# CoffeeMakersch.net
KiCad netlist of a schematic drawn in EAGLE
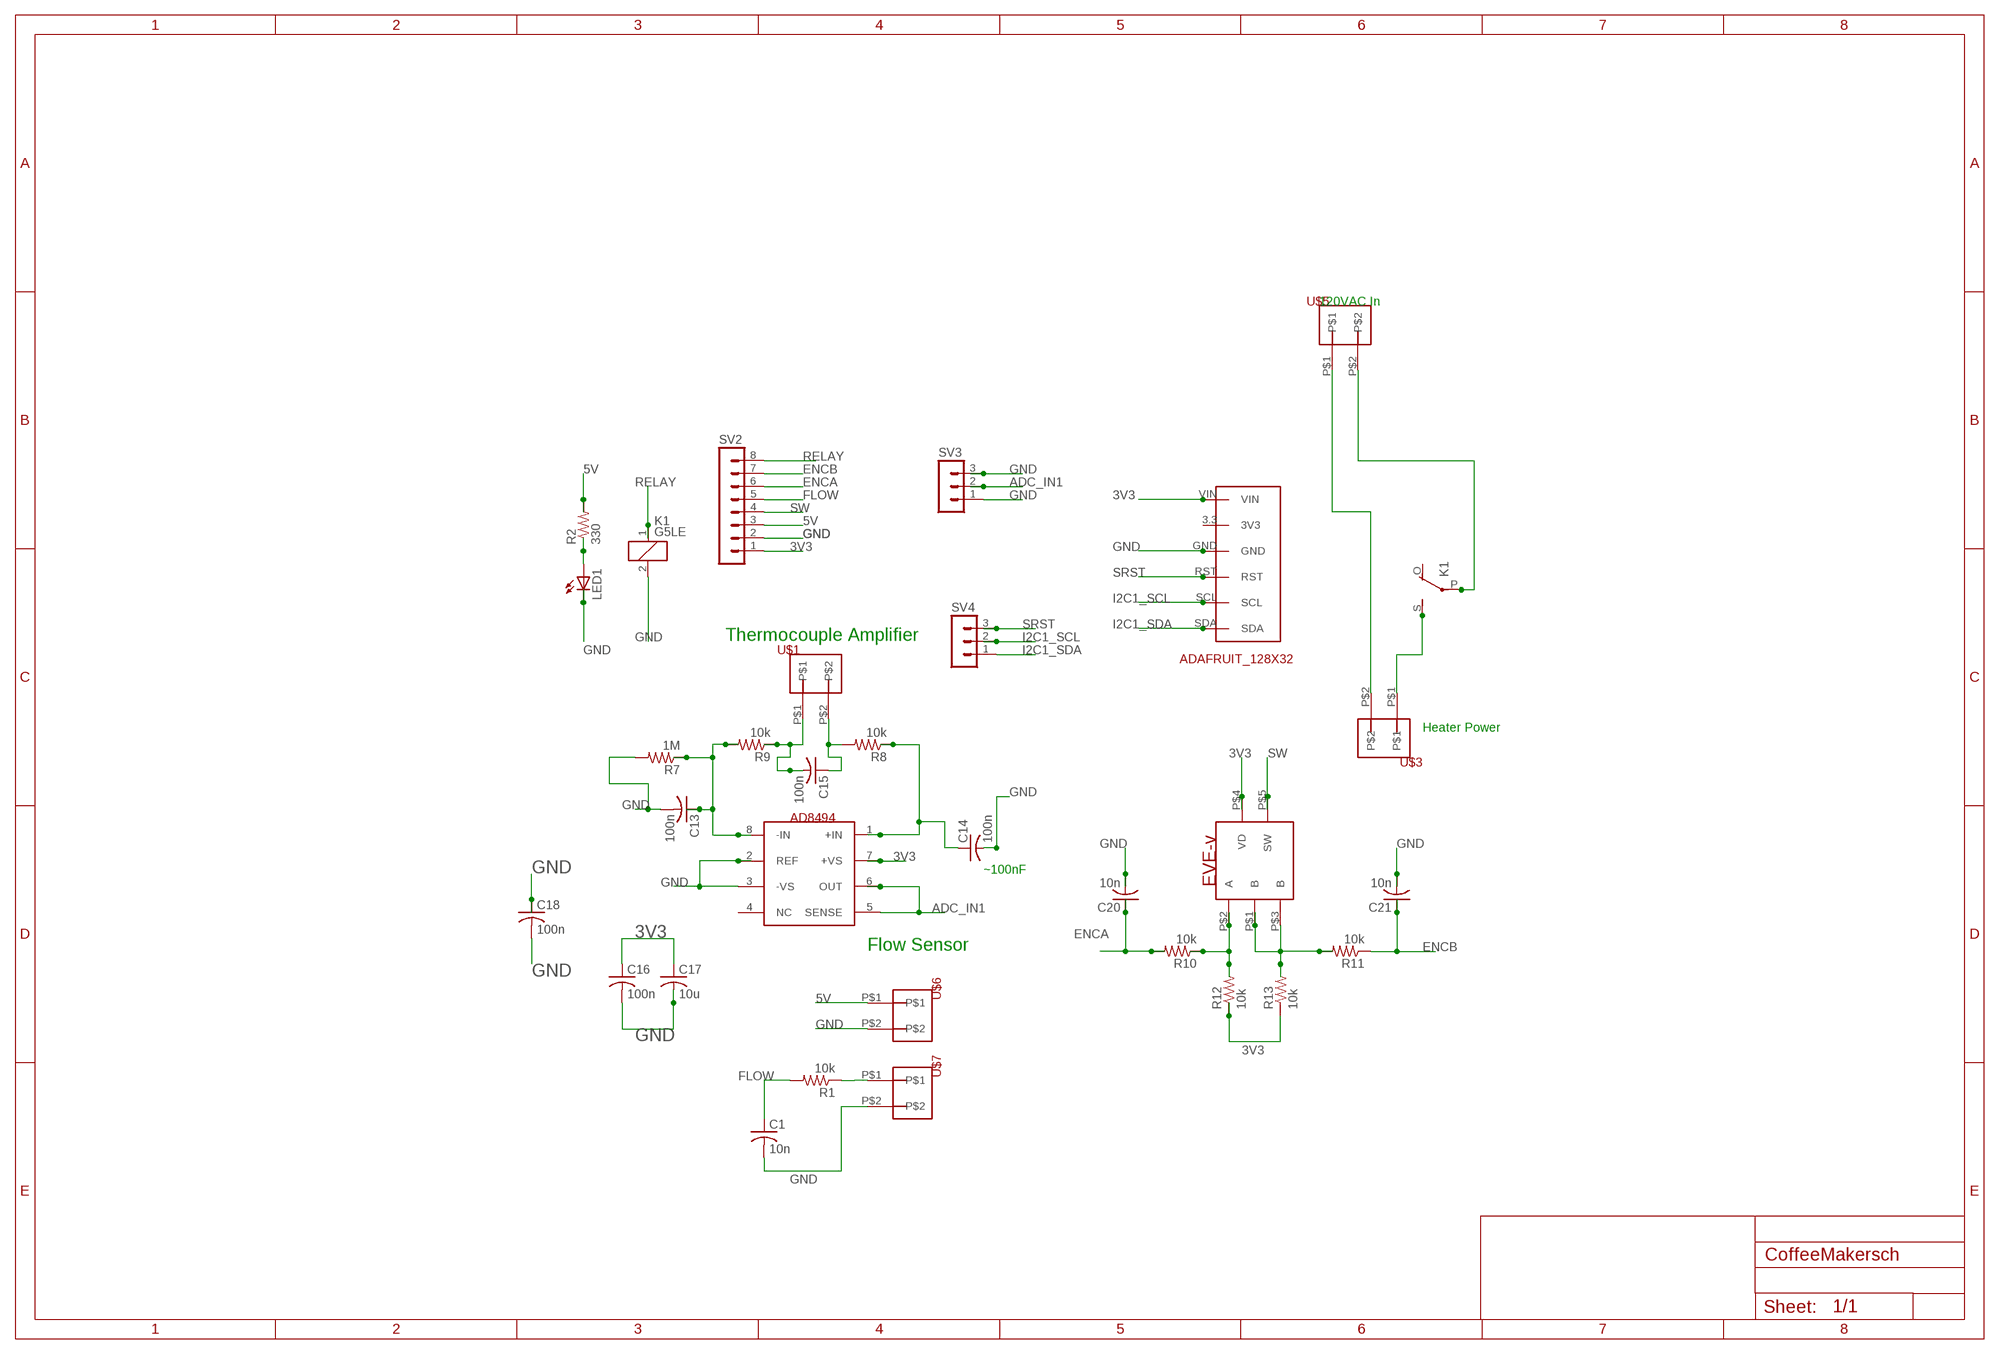
[diagram p0: schematic, sheet 1]

(export (version "E")
  (design (tool "Eeschema 10.0.6"))
  (components
    (comp (ref "C1")
      (value "10n")
      (footprint "eagle-import:C0805")
      (libsource (lib "eagle-import") (part "C-USC0805"))
    )
    (comp (ref "C13")
      (value "100n")
      (footprint "eagle-import:C0805")
      (libsource (lib "eagle-import") (part "C-USC0805"))
    )
    (comp (ref "C14")
      (value "100n")
      (footprint "eagle-import:C0805")
      (libsource (lib "eagle-import") (part "C-USC0805"))
    )
    (comp (ref "C15")
      (value "100n")
      (footprint "eagle-import:C0805")
      (libsource (lib "eagle-import") (part "C-USC0805"))
    )
    (comp (ref "C16")
      (value "100n")
      (footprint "eagle-import:C0805")
      (libsource (lib "eagle-import") (part "C-USC0805"))
    )
    (comp (ref "C17")
      (value "10u")
      (footprint "eagle-import:C0805")
      (libsource (lib "eagle-import") (part "C-USC0805"))
    )
    (comp (ref "C18")
      (value "100n")
      (footprint "eagle-import:C0805")
      (libsource (lib "eagle-import") (part "C-USC0805"))
    )
    (comp (ref "C20")
      (value "10n")
      (footprint "eagle-import:C0805")
      (libsource (lib "eagle-import") (part "C-USC0805"))
    )
    (comp (ref "C21")
      (value "10n")
      (footprint "eagle-import:C0805")
      (libsource (lib "eagle-import") (part "C-USC0805"))
    )
    (comp (ref "K1")
      (value "G5LE")
      (footprint "eagle-import:G5LE")
      (libsource (lib "eagle-import") (part "G5LE"))
    )
    (comp (ref "LED1")
      (value "LEDCHIPLED_1206")
      (footprint "eagle-import:CHIPLED_1206")
      (libsource (lib "eagle-import") (part "LEDCHIPLED_1206"))
    )
    (comp (ref "R1")
      (value "10k")
      (footprint "eagle-import:R0805")
      (libsource (lib "eagle-import") (part "R-US_R0805"))
    )
    (comp (ref "R2")
      (value "330")
      (footprint "eagle-import:R0805")
      (libsource (lib "eagle-import") (part "R-US_R0805"))
    )
    (comp (ref "R7")
      (value "1M")
      (footprint "eagle-import:R0805")
      (libsource (lib "eagle-import") (part "R-US_R0805"))
    )
    (comp (ref "R8")
      (value "10k")
      (footprint "eagle-import:R0805")
      (libsource (lib "eagle-import") (part "R-US_R0805"))
    )
    (comp (ref "R9")
      (value "10k")
      (footprint "eagle-import:R0805")
      (libsource (lib "eagle-import") (part "R-US_R0805"))
    )
    (comp (ref "R10")
      (value "10k")
      (footprint "eagle-import:R0805")
      (libsource (lib "eagle-import") (part "R-US_R0805"))
    )
    (comp (ref "R11")
      (value "10k")
      (footprint "eagle-import:R0805")
      (libsource (lib "eagle-import") (part "R-US_R0805"))
    )
    (comp (ref "R12")
      (value "10k")
      (footprint "eagle-import:R0805")
      (libsource (lib "eagle-import") (part "R-US_R0805"))
    )
    (comp (ref "R13")
      (value "10k")
      (footprint "eagle-import:R0805")
      (libsource (lib "eagle-import") (part "R-US_R0805"))
    )
    (comp (ref "SV2")
      (value "MA08-1")
      (footprint "eagle-import:MA08-1")
      (libsource (lib "eagle-import") (part "MA08-1"))
    )
    (comp (ref "SV3")
      (value "MA03-1")
      (footprint "eagle-import:MA03-1")
      (libsource (lib "eagle-import") (part "MA03-1"))
    )
    (comp (ref "SV4")
      (value "MA03-1")
      (footprint "eagle-import:MA03-1")
      (libsource (lib "eagle-import") (part "MA03-1"))
    )
    (comp (ref "U$1")
      (value "5TERM")
      (footprint "eagle-import:5TERM")
      (libsource (lib "eagle-import") (part "5TERM"))
    )
    (comp (ref "U$2")
      (value "AD8494")
      (footprint "eagle-import:TSSOP8")
      (libsource (lib "eagle-import") (part "AD8494"))
    )
    (comp (ref "U$3")
      (value "5TERM")
      (footprint "eagle-import:5TERM")
      (libsource (lib "eagle-import") (part "5TERM"))
    )
    (comp (ref "U$4")
      (value "EVE-V")
      (footprint "eagle-import:EVE-V")
      (libsource (lib "eagle-import") (part "EVE-V"))
    )
    (comp (ref "U$5")
      (value "5TERM")
      (footprint "eagle-import:5TERM")
      (libsource (lib "eagle-import") (part "5TERM"))
    )
    (comp (ref "U$6")
      (value "5TERM")
      (footprint "eagle-import:5TERM")
      (libsource (lib "eagle-import") (part "5TERM"))
    )
    (comp (ref "U$7")
      (value "5TERM")
      (footprint "eagle-import:5TERM")
      (libsource (lib "eagle-import") (part "5TERM"))
    )
    (comp (ref "U$11")
      (value "ADAFRUIT_128X32")
      (footprint "eagle-import:ADAFRUIT128X32")
      (libsource (lib "eagle-import") (part "ADAFRUIT_128X32"))
    )
  )
  (nets
    (net (code "1") (name "/3V3") (class "Default")
      (node (ref "C16") (pin "1") (pinfunction "1_1") (pintype "passive"))
      (node (ref "C17") (pin "1") (pinfunction "1_1") (pintype "passive"))
      (node (ref "R12") (pin "1") (pinfunction "1_1") (pintype "passive"))
      (node (ref "R13") (pin "1") (pinfunction "1_1") (pintype "passive"))
      (node (ref "SV2") (pin "1") (pinfunction "1_1") (pintype "passive"))
      (node (ref "U$11") (pin "VIN") (pinfunction "VIN_VIN") (pintype "bidirectional"))
      (node (ref "U$2") (pin "7") (pinfunction "+VS_7") (pintype "bidirectional"))
      (node (ref "U$4") (pin "P$4") (pinfunction "VD_P$4") (pintype "bidirectional"))
    )
    (net (code "2") (name "/5V") (class "Default")
      (node (ref "R2") (pin "2") (pinfunction "2_2") (pintype "passive"))
      (node (ref "SV2") (pin "3") (pinfunction "3_3") (pintype "passive"))
      (node (ref "U$6") (pin "P$1") (pinfunction "P$1_P$1") (pintype "bidirectional"))
    )
    (net (code "3") (name "/ADC_IN1") (class "Default")
      (node (ref "SV3") (pin "2") (pinfunction "2_2") (pintype "passive"))
      (node (ref "U$2") (pin "5") (pinfunction "SENSE_5") (pintype "bidirectional"))
      (node (ref "U$2") (pin "6") (pinfunction "OUT_6") (pintype "bidirectional"))
    )
    (net (code "4") (name "/ENCA") (class "Default")
      (node (ref "C20") (pin "1") (pinfunction "1_1") (pintype "passive"))
      (node (ref "R10") (pin "2") (pinfunction "2_2") (pintype "passive"))
      (node (ref "SV2") (pin "6") (pinfunction "6_6") (pintype "passive"))
    )
    (net (code "5") (name "/ENCB") (class "Default")
      (node (ref "C21") (pin "1") (pinfunction "1_1") (pintype "passive"))
      (node (ref "R11") (pin "1") (pinfunction "1_1") (pintype "passive"))
      (node (ref "SV2") (pin "7") (pinfunction "7_7") (pintype "passive"))
    )
    (net (code "6") (name "/FLOW") (class "Default")
      (node (ref "C1") (pin "1") (pinfunction "1_1") (pintype "passive"))
      (node (ref "R1") (pin "2") (pinfunction "2_2") (pintype "passive"))
      (node (ref "SV2") (pin "5") (pinfunction "5_5") (pintype "passive"))
    )
    (net (code "7") (name "/GND") (class "Default")
      (node (ref "C1") (pin "2") (pinfunction "2_2") (pintype "passive"))
      (node (ref "C13") (pin "2") (pinfunction "2_2") (pintype "passive"))
      (node (ref "C14") (pin "2") (pinfunction "2_2") (pintype "passive"))
      (node (ref "C16") (pin "2") (pinfunction "2_2") (pintype "passive"))
      (node (ref "C17") (pin "2") (pinfunction "2_2") (pintype "passive"))
      (node (ref "C18") (pin "1") (pinfunction "1_1") (pintype "passive"))
      (node (ref "C18") (pin "2") (pinfunction "2_2") (pintype "passive"))
      (node (ref "C20") (pin "2") (pinfunction "2_2") (pintype "passive"))
      (node (ref "C21") (pin "2") (pinfunction "2_2") (pintype "passive"))
      (node (ref "K1") (pin "2") (pinfunction "2_2") (pintype "passive"))
      (node (ref "LED1") (pin "C") (pinfunction "C_C") (pintype "passive"))
      (node (ref "R7") (pin "2") (pinfunction "2_2") (pintype "passive"))
      (node (ref "SV2") (pin "2") (pinfunction "2_2") (pintype "passive"))
      (node (ref "SV3") (pin "1") (pinfunction "1_1") (pintype "passive"))
      (node (ref "SV3") (pin "3") (pinfunction "3_3") (pintype "passive"))
      (node (ref "U$11") (pin "GND") (pinfunction "GND_GND") (pintype "bidirectional"))
      (node (ref "U$2") (pin "2") (pinfunction "REF_2") (pintype "bidirectional"))
      (node (ref "U$2") (pin "3") (pinfunction "-VS_3") (pintype "bidirectional"))
      (node (ref "U$6") (pin "P$2") (pinfunction "P$2_P$2") (pintype "bidirectional"))
      (node (ref "U$7") (pin "P$2") (pinfunction "P$2_P$2") (pintype "bidirectional"))
    )
    (net (code "8") (name "/I2C1_SCL") (class "Default")
      (node (ref "SV4") (pin "2") (pinfunction "2_2") (pintype "passive"))
      (node (ref "U$11") (pin "SCL") (pinfunction "SCL_SCL") (pintype "bidirectional"))
    )
    (net (code "9") (name "/I2C1_SDA") (class "Default")
      (node (ref "SV4") (pin "1") (pinfunction "1_1") (pintype "passive"))
      (node (ref "U$11") (pin "SDA") (pinfunction "SDA_SDA") (pintype "bidirectional"))
    )
    (net (code "10") (name "/RELAY") (class "Default")
      (node (ref "K1") (pin "1") (pinfunction "1_1") (pintype "passive"))
      (node (ref "SV2") (pin "8") (pinfunction "8_8") (pintype "passive"))
    )
    (net (code "11") (name "/SRST") (class "Default")
      (node (ref "SV4") (pin "3") (pinfunction "3_3") (pintype "passive"))
      (node (ref "U$11") (pin "RST") (pinfunction "RST_RST") (pintype "bidirectional"))
    )
    (net (code "12") (name "/SW") (class "Default")
      (node (ref "SV2") (pin "4") (pinfunction "4_4") (pintype "passive"))
      (node (ref "U$4") (pin "P$5") (pinfunction "SW_P$5") (pintype "bidirectional"))
    )
    (net (code "13") (name "Net-(C15-Pad1)") (class "Default")
      (node (ref "C15") (pin "1") (pinfunction "1_1") (pintype "passive"))
      (node (ref "R8") (pin "2") (pinfunction "2_2") (pintype "passive"))
      (node (ref "U$1") (pin "P$2") (pinfunction "P$2_P$2") (pintype "bidirectional"))
    )
    (net (code "14") (name "Net-(C15-Pad2)") (class "Default")
      (node (ref "C15") (pin "2") (pinfunction "2_2") (pintype "passive"))
      (node (ref "R9") (pin "1") (pinfunction "1_1") (pintype "passive"))
      (node (ref "U$1") (pin "P$1") (pinfunction "P$1_P$1") (pintype "bidirectional"))
    )
    (net (code "15") (name "Net-(K1-PadP)") (class "Default")
      (node (ref "K1") (pin "P") (pinfunction "P_P") (pintype "passive"))
      (node (ref "U$5") (pin "P$2") (pinfunction "P$2_P$2") (pintype "bidirectional"))
    )
    (net (code "16") (name "Net-(K1-PadS)") (class "Default")
      (node (ref "K1") (pin "S") (pinfunction "S_S") (pintype "passive"))
      (node (ref "U$3") (pin "P$1") (pinfunction "P$1_P$1") (pintype "bidirectional"))
    )
    (net (code "17") (name "Net-(LED1-PadA)") (class "Default")
      (node (ref "LED1") (pin "A") (pinfunction "A_A") (pintype "passive"))
      (node (ref "R2") (pin "1") (pinfunction "1_1") (pintype "passive"))
    )
    (net (code "18") (name "Net-(R1-Pad1)") (class "Default")
      (node (ref "R1") (pin "1") (pinfunction "1_1") (pintype "passive"))
      (node (ref "U$7") (pin "P$1") (pinfunction "P$1_P$1") (pintype "bidirectional"))
    )
    (net (code "19") (name "Net-(R11-Pad2)") (class "Default")
      (node (ref "R11") (pin "2") (pinfunction "2_2") (pintype "passive"))
      (node (ref "R13") (pin "2") (pinfunction "2_2") (pintype "passive"))
      (node (ref "U$4") (pin "P$1") (pinfunction "B_P$1") (pintype "bidirectional"))
      (node (ref "U$4") (pin "P$3") (pinfunction "B_P$3") (pintype "bidirectional"))
    )
    (net (code "20") (name "Net-(U$2-+IN)") (class "Default")
      (node (ref "C14") (pin "1") (pinfunction "1_1") (pintype "passive"))
      (node (ref "R8") (pin "1") (pinfunction "1_1") (pintype "passive"))
      (node (ref "U$2") (pin "1") (pinfunction "+IN_1") (pintype "bidirectional"))
    )
    (net (code "21") (name "Net-(U$2--IN)") (class "Default")
      (node (ref "C13") (pin "1") (pinfunction "1_1") (pintype "passive"))
      (node (ref "R7") (pin "1") (pinfunction "1_1") (pintype "passive"))
      (node (ref "R9") (pin "2") (pinfunction "2_2") (pintype "passive"))
      (node (ref "U$2") (pin "8") (pinfunction "-IN_8") (pintype "bidirectional"))
    )
    (net (code "22") (name "Net-(U$3-PadP$2)") (class "Default")
      (node (ref "U$3") (pin "P$2") (pinfunction "P$2_P$2") (pintype "bidirectional"))
      (node (ref "U$5") (pin "P$1") (pinfunction "P$1_P$1") (pintype "bidirectional"))
    )
    (net (code "23") (name "Net-(U$4-A)") (class "Default")
      (node (ref "R10") (pin "1") (pinfunction "1_1") (pintype "passive"))
      (node (ref "R12") (pin "2") (pinfunction "2_2") (pintype "passive"))
      (node (ref "U$4") (pin "P$2") (pinfunction "A_P$2") (pintype "bidirectional"))
    )
    (net (code "24") (name "unconnected-(K1-PadO)") (class "Default")
      (node (ref "K1") (pin "O") (pinfunction "O_O") (pintype "passive"))
    )
    (net (code "25") (name "unconnected-(U$2-NC-Pad4)") (class "Default")
      (node (ref "U$2") (pin "4") (pinfunction "NC_4") (pintype "bidirectional"))
    )
    (net (code "26") (name "unconnected-(U$11-3V3-Pad3.3)") (class "Default")
      (node (ref "U$11") (pin "3.3") (pinfunction "3V3_3.3") (pintype "bidirectional"))
    )
  )
)
